# ProPrj_LED__2025-12-14-09-48-45.net
KiCad netlist of a schematic drawn in EasyEDA Pro
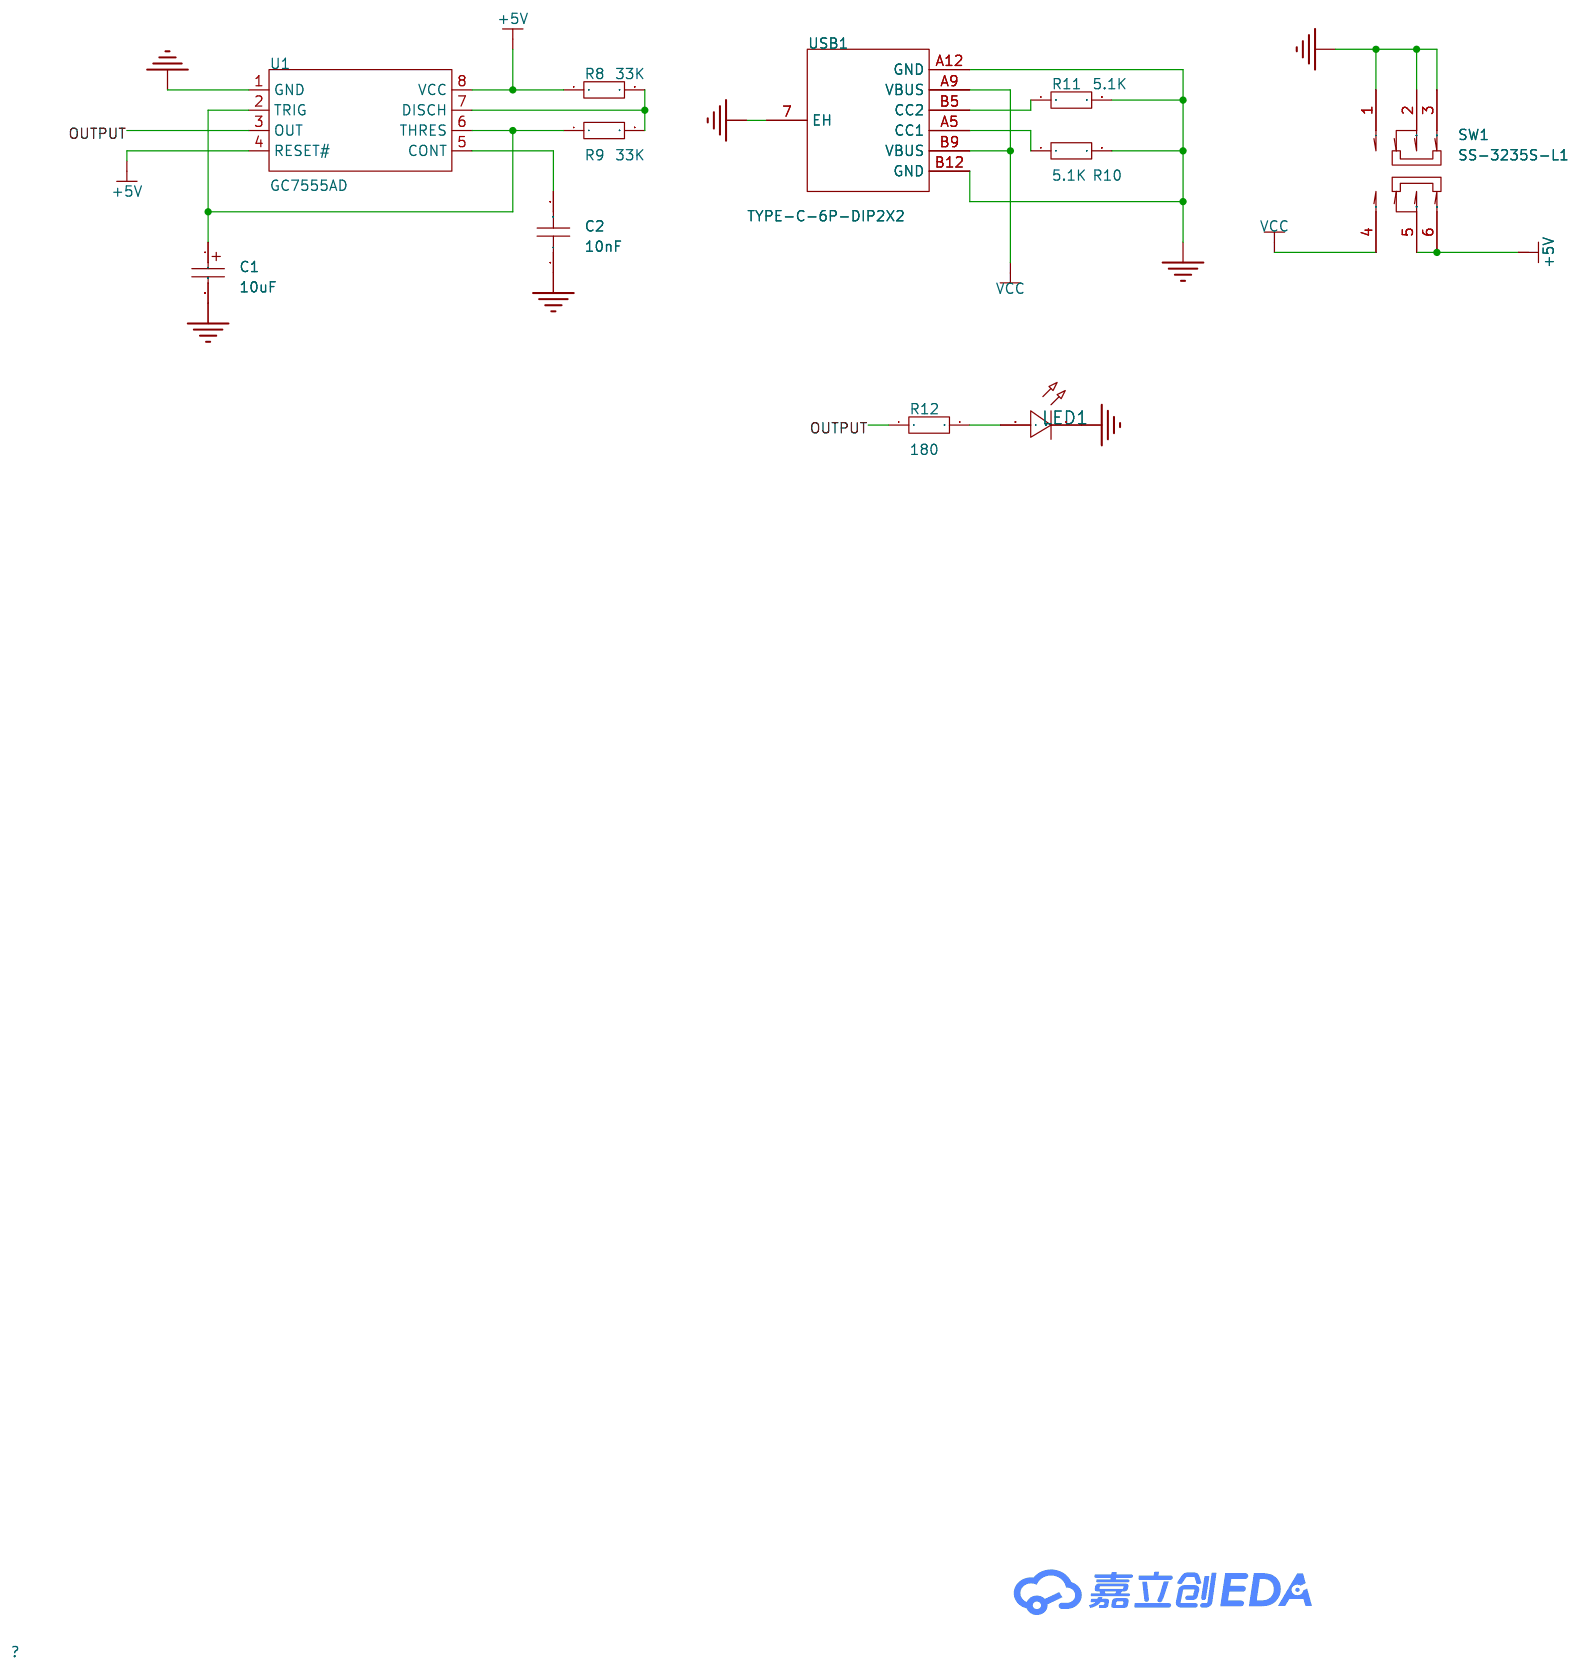
[diagram p0: schematic sheet]

(export (version "E")
  (design (tool "Eeschema 10.0.6"))
  (components
    (comp (ref "C1")
      (value "10uF")
      (footprint "easyedapro:C_Ele_SMD_3x5.4mm")
      (libsource (lib "easyedapro") (part "CAP"))
    )
    (comp (ref "C2")
      (value "10nF")
      (footprint "easyedapro:C0603")
      (libsource (lib "easyedapro") (part "Capacitance"))
    )
    (comp (ref "LED1")
      (value "~")
      (footprint "easyedapro:LED_0603")
      (libsource (lib "easyedapro") (part "LED_R"))
    )
    (comp (ref "R8") (value "33K") (footprint "easyedapro:R0805") (libsource (lib "easyedapro") (part "电阻")))
    (comp (ref "R9") (value "33K") (footprint "easyedapro:R0805") (libsource (lib "easyedapro") (part "电阻")))
    (comp (ref "R10")
      (value "5.1K")
      (footprint "easyedapro:R0805")
      (libsource (lib "easyedapro") (part "电阻"))
    )
    (comp (ref "R11")
      (value "5.1K")
      (footprint "easyedapro:R0805")
      (libsource (lib "easyedapro") (part "电阻"))
    )
    (comp (ref "R12") (value "180") (footprint "easyedapro:R0805") (libsource (lib "easyedapro") (part "电阻")))
    (comp (ref "SW1")
      (value "SS-3235S-L1")
      (footprint "easyedapro:SW-SMD_SS-3235S-LX")
      (description "电路结构:双刀双掷;安装方式:卧贴;开关颜色:黑色;额定电流:50mA;额定电压:12V;工作寿命:1万次;")
      (fields (field (name "Manufacturer") "XKB Connection(中国星坤)"))
      (libsource (lib "easyedapro") (part "SS-3235S-L1"))
    )
    (comp (ref "U1")
      (value "GC7555AD")
      (footprint "easyedapro:PDIP-8_L9.5-W6.4-P2.54-LS7.6-BL")
      (description "通用计时器：时基电路；计时；脉冲产生；满足用户（至少工业级）自主可控的需求。")
      (fields (field (name "Manufacturer") "Sungine(双竞集成)"))
      (libsource (lib "easyedapro") (part "GC7555AD"))
    )
    (comp (ref "USB1")
      (value "TYPE-C-6P-DIP2X2")
      (footprint "easyedapro:TYPE-C-SMD_TYPE-C-6P")
      (libsource (lib "easyedapro") (part "TYPE-C-6P-DIP2X2"))
    )
  )
  (nets
    (net (code "1") (name "+5V") (class "Default")
      (node (ref "R8") (pin "1") (pinfunction "1_1") (pintype "input"))
      (node (ref "SW1") (pin "5") (pinfunction "5_5") (pintype "unspecified"))
      (node (ref "SW1") (pin "6") (pinfunction "6_6") (pintype "unspecified"))
      (node (ref "U1") (pin "4") (pinfunction "RESET#_4") (pintype "unspecified"))
      (node (ref "U1") (pin "8") (pinfunction "VCC_8") (pintype "unspecified"))
    )
    (net (code "2") (name "/OUTPUT") (class "Default")
      (node (ref "R12") (pin "1") (pinfunction "1_1") (pintype "input"))
      (node (ref "U1") (pin "3") (pinfunction "OUT_3") (pintype "unspecified"))
    )
    (net (code "3") (name "GND") (class "Default")
      (node (ref "C1") (pin "2") (pinfunction "2_2") (pintype "input"))
      (node (ref "C2") (pin "1") (pinfunction "1_1") (pintype "input"))
      (node (ref "LED1") (pin "1") (pinfunction "C_1") (pintype "input"))
      (node (ref "R10") (pin "2") (pinfunction "2_2") (pintype "input"))
      (node (ref "R11") (pin "2") (pinfunction "2_2") (pintype "input"))
      (node (ref "SW1") (pin "1") (pinfunction "1_1") (pintype "unspecified"))
      (node (ref "SW1") (pin "2") (pinfunction "2_2") (pintype "unspecified"))
      (node (ref "SW1") (pin "3") (pinfunction "3_3") (pintype "unspecified"))
      (node (ref "U1") (pin "1") (pinfunction "GND_1") (pintype "unspecified"))
      (node (ref "USB1") (pin "7") (pinfunction "EH_7") (pintype "unspecified"))
      (node (ref "USB1") (pin "A12") (pinfunction "GND_A12") (pintype "unspecified"))
      (node (ref "USB1") (pin "B12") (pinfunction "GND_B12") (pintype "unspecified"))
    )
    (net (code "4") (name "Net-(LED1-A)") (class "Default")
      (node (ref "LED1") (pin "2") (pinfunction "A_2") (pintype "input"))
      (node (ref "R12") (pin "2") (pinfunction "2_2") (pintype "input"))
    )
    (net (code "5") (name "Net-(U1-CONT)") (class "Default")
      (node (ref "C2") (pin "2") (pinfunction "2_2") (pintype "input"))
      (node (ref "U1") (pin "5") (pinfunction "CONT_5") (pintype "unspecified"))
    )
    (net (code "6") (name "Net-(U1-DISCH)") (class "Default")
      (node (ref "R8") (pin "2") (pinfunction "2_2") (pintype "input"))
      (node (ref "R9") (pin "2") (pinfunction "2_2") (pintype "input"))
      (node (ref "U1") (pin "7") (pinfunction "DISCH_7") (pintype "unspecified"))
    )
    (net (code "7") (name "Net-(U1-THRES)") (class "Default")
      (node (ref "C1") (pin "1") (pinfunction "1_1") (pintype "input"))
      (node (ref "R9") (pin "1") (pinfunction "1_1") (pintype "input"))
      (node (ref "U1") (pin "2") (pinfunction "TRIG_2") (pintype "unspecified"))
      (node (ref "U1") (pin "6") (pinfunction "THRES_6") (pintype "unspecified"))
    )
    (net (code "8") (name "Net-(USB1-CC1)") (class "Default")
      (node (ref "R10") (pin "1") (pinfunction "1_1") (pintype "input"))
      (node (ref "USB1") (pin "A5") (pinfunction "CC1_A5") (pintype "unspecified"))
    )
    (net (code "9") (name "Net-(USB1-CC2)") (class "Default")
      (node (ref "R11") (pin "1") (pinfunction "1_1") (pintype "input"))
      (node (ref "USB1") (pin "B5") (pinfunction "CC2_B5") (pintype "unspecified"))
    )
    (net (code "10") (name "VCC") (class "Default")
      (node (ref "SW1") (pin "4") (pinfunction "4_4") (pintype "unspecified"))
      (node (ref "USB1") (pin "A9") (pinfunction "VBUS_A9") (pintype "unspecified"))
      (node (ref "USB1") (pin "B9") (pinfunction "VBUS_B9") (pintype "unspecified"))
    )
  )
)
